# motor_driver.net
KiCad netlist of a schematic drawn in EAGLE
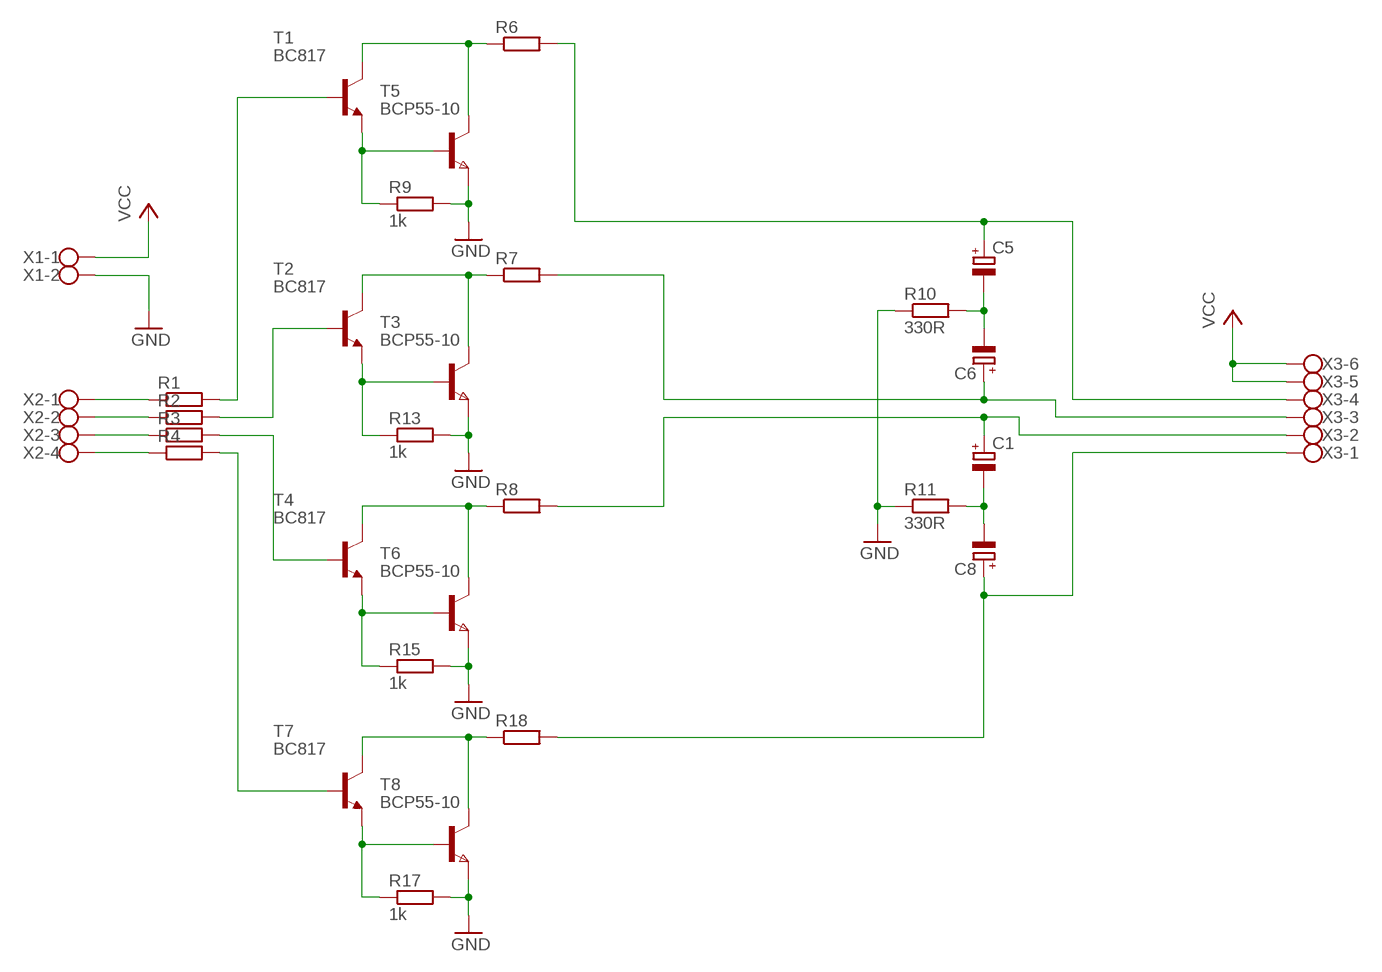
[diagram p0: schematic, sheet 1]

(export (version "E")
  (design (tool "Eeschema 10.0.6"))
  (components
    (comp (ref "C1")
      (value "CPOL-EU153CLV-0807")
      (footprint "eagle-import:153CLV-0807")
      (libsource (lib "eagle-import") (part "CPOL-EU153CLV-0807"))
    )
    (comp (ref "C5")
      (value "CPOL-EU153CLV-0807")
      (footprint "eagle-import:153CLV-0807")
      (libsource (lib "eagle-import") (part "CPOL-EU153CLV-0807"))
    )
    (comp (ref "C6")
      (value "CPOL-EU153CLV-0807")
      (footprint "eagle-import:153CLV-0807")
      (libsource (lib "eagle-import") (part "CPOL-EU153CLV-0807"))
    )
    (comp (ref "C8")
      (value "CPOL-EU153CLV-0807")
      (footprint "eagle-import:153CLV-0807")
      (libsource (lib "eagle-import") (part "CPOL-EU153CLV-0807"))
    )
    (comp (ref "R1")
      (value "R-EU_M1206")
      (footprint "eagle-import:M1206")
      (libsource (lib "eagle-import") (part "R-EU_M1206"))
    )
    (comp (ref "R2")
      (value "R-EU_M1206")
      (footprint "eagle-import:M1206")
      (libsource (lib "eagle-import") (part "R-EU_M1206"))
    )
    (comp (ref "R3")
      (value "R-EU_M1206")
      (footprint "eagle-import:M1206")
      (libsource (lib "eagle-import") (part "R-EU_M1206"))
    )
    (comp (ref "R4")
      (value "R-EU_M1206")
      (footprint "eagle-import:M1206")
      (libsource (lib "eagle-import") (part "R-EU_M1206"))
    )
    (comp (ref "R6")
      (value "R-EU_0922/22")
      (footprint "eagle-import:0922_22")
      (libsource (lib "eagle-import") (part "R-EU_0922/22"))
    )
    (comp (ref "R7")
      (value "R-EU_0922/22")
      (footprint "eagle-import:0922_22")
      (libsource (lib "eagle-import") (part "R-EU_0922/22"))
    )
    (comp (ref "R8")
      (value "R-EU_0922/22")
      (footprint "eagle-import:0922_22")
      (libsource (lib "eagle-import") (part "R-EU_0922/22"))
    )
    (comp (ref "R9")
      (value "1k")
      (footprint "eagle-import:M1206")
      (libsource (lib "eagle-import") (part "R-EU_M1206"))
    )
    (comp (ref "R10")
      (value "330R")
      (footprint "eagle-import:M1206")
      (libsource (lib "eagle-import") (part "R-EU_M1206"))
    )
    (comp (ref "R11")
      (value "330R")
      (footprint "eagle-import:M1206")
      (libsource (lib "eagle-import") (part "R-EU_M1206"))
    )
    (comp (ref "R13")
      (value "1k")
      (footprint "eagle-import:M1206")
      (libsource (lib "eagle-import") (part "R-EU_M1206"))
    )
    (comp (ref "R15")
      (value "1k")
      (footprint "eagle-import:M1206")
      (libsource (lib "eagle-import") (part "R-EU_M1206"))
    )
    (comp (ref "R17")
      (value "1k")
      (footprint "eagle-import:M1206")
      (libsource (lib "eagle-import") (part "R-EU_M1206"))
    )
    (comp (ref "R18")
      (value "R-EU_0922/22")
      (footprint "eagle-import:0922_22")
      (libsource (lib "eagle-import") (part "R-EU_0922/22"))
    )
    (comp (ref "T1")
      (value "BC817")
      (footprint "eagle-import:SOT23-BEC")
      (libsource (lib "eagle-import") (part "-NPN-SOT23-BECBC817-25"))
    )
    (comp (ref "T2")
      (value "BC817")
      (footprint "eagle-import:SOT23-BEC")
      (libsource (lib "eagle-import") (part "-NPN-SOT23-BECBC817-25"))
    )
    (comp (ref "T3")
      (value "BCP55-10")
      (footprint "eagle-import:SOT223")
      (fields (field (name "MPN") "DJT4031N-13"))
      (libsource (lib "eagle-import") (part "NPNSOT223"))
    )
    (comp (ref "T4")
      (value "BC817")
      (footprint "eagle-import:SOT23-BEC")
      (libsource (lib "eagle-import") (part "-NPN-SOT23-BECBC817-25"))
    )
    (comp (ref "T5")
      (value "BCP55-10")
      (footprint "eagle-import:SOT223")
      (fields (field (name "MPN") "DJT4031N-13"))
      (libsource (lib "eagle-import") (part "NPNSOT223"))
    )
    (comp (ref "T6")
      (value "BCP55-10")
      (footprint "eagle-import:SOT223")
      (fields (field (name "MPN") "DJT4031N-13"))
      (libsource (lib "eagle-import") (part "NPNSOT223"))
    )
    (comp (ref "T7")
      (value "BC817")
      (footprint "eagle-import:SOT23-BEC")
      (libsource (lib "eagle-import") (part "-NPN-SOT23-BECBC817-25"))
    )
    (comp (ref "T8")
      (value "BCP55-10")
      (footprint "eagle-import:SOT223")
      (fields (field (name "MPN") "DJT4031N-13"))
      (libsource (lib "eagle-import") (part "NPNSOT223"))
    )
    (comp (ref "X1")
      (value "W237-102")
      (footprint "eagle-import:W237-102")
      (fields (field (name "MPN") "237-102"))
      (libsource (lib "eagle-import") (part "W237-102"))
    )
    (comp (ref "X2")
      (value "W237-4")
      (footprint "eagle-import:W237-4")
      (libsource (lib "eagle-import") (part "W237-4"))
    )
    (comp (ref "X3")
      (value "W237-6")
      (footprint "eagle-import:W237-6")
      (libsource (lib "eagle-import") (part "W237-6"))
    )
  )
  (nets
    (net (code "1") (name "GND") (class "Default")
      (node (ref "R10") (pin "1") (pinfunction "1_1") (pintype "passive"))
      (node (ref "R11") (pin "1") (pinfunction "1_1") (pintype "passive"))
      (node (ref "R13") (pin "2") (pinfunction "2_2") (pintype "passive"))
      (node (ref "R15") (pin "2") (pinfunction "2_2") (pintype "passive"))
      (node (ref "R17") (pin "2") (pinfunction "2_2") (pintype "passive"))
      (node (ref "R9") (pin "2") (pinfunction "2_2") (pintype "passive"))
      (node (ref "T3") (pin "3") (pinfunction "E_3") (pintype "passive"))
      (node (ref "T5") (pin "3") (pinfunction "E_3") (pintype "passive"))
      (node (ref "T6") (pin "3") (pinfunction "E_3") (pintype "passive"))
      (node (ref "T8") (pin "3") (pinfunction "E_3") (pintype "passive"))
      (node (ref "X1") (pin "2") (pinfunction "KL_2") (pintype "passive"))
    )
    (net (code "2") (name "Net-(C1-Pad-)") (class "Default")
      (node (ref "C1") (pin "-") (pinfunction "-_-") (pintype "passive"))
      (node (ref "C8") (pin "-") (pinfunction "-_-") (pintype "passive"))
      (node (ref "R11") (pin "2") (pinfunction "2_2") (pintype "passive"))
    )
    (net (code "3") (name "Net-(C5-Pad-)") (class "Default")
      (node (ref "C5") (pin "-") (pinfunction "-_-") (pintype "passive"))
      (node (ref "C6") (pin "-") (pinfunction "-_-") (pintype "passive"))
      (node (ref "R10") (pin "2") (pinfunction "2_2") (pintype "passive"))
    )
    (net (code "4") (name "Net-(R1-Pad2)") (class "Default")
      (node (ref "R1") (pin "2") (pinfunction "2_2") (pintype "passive"))
      (node (ref "T1") (pin "B") (pinfunction "B_B") (pintype "passive"))
    )
    (net (code "5") (name "Net-(R2-Pad2)") (class "Default")
      (node (ref "R2") (pin "2") (pinfunction "2_2") (pintype "passive"))
      (node (ref "T2") (pin "B") (pinfunction "B_B") (pintype "passive"))
    )
    (net (code "6") (name "Net-(R3-Pad2)") (class "Default")
      (node (ref "R3") (pin "2") (pinfunction "2_2") (pintype "passive"))
      (node (ref "T4") (pin "B") (pinfunction "B_B") (pintype "passive"))
    )
    (net (code "7") (name "Net-(R4-Pad2)") (class "Default")
      (node (ref "R4") (pin "2") (pinfunction "2_2") (pintype "passive"))
      (node (ref "T7") (pin "B") (pinfunction "B_B") (pintype "passive"))
    )
    (net (code "8") (name "Net-(R6-Pad1)") (class "Default")
      (node (ref "R6") (pin "1") (pinfunction "1_1") (pintype "passive"))
      (node (ref "T1") (pin "C") (pinfunction "C_C") (pintype "passive"))
      (node (ref "T5") (pin "2") (pinfunction "C_2") (pintype "passive"))
      (node (ref "T5") (pin "4") (pinfunction "C_4") (pintype "passive"))
    )
    (net (code "9") (name "Net-(R7-Pad1)") (class "Default")
      (node (ref "R7") (pin "1") (pinfunction "1_1") (pintype "passive"))
      (node (ref "T2") (pin "C") (pinfunction "C_C") (pintype "passive"))
      (node (ref "T3") (pin "2") (pinfunction "C_2") (pintype "passive"))
      (node (ref "T3") (pin "4") (pinfunction "C_4") (pintype "passive"))
    )
    (net (code "10") (name "Net-(R8-Pad1)") (class "Default")
      (node (ref "R8") (pin "1") (pinfunction "1_1") (pintype "passive"))
      (node (ref "T4") (pin "C") (pinfunction "C_C") (pintype "passive"))
      (node (ref "T6") (pin "2") (pinfunction "C_2") (pintype "passive"))
      (node (ref "T6") (pin "4") (pinfunction "C_4") (pintype "passive"))
    )
    (net (code "11") (name "Net-(R18-Pad1)") (class "Default")
      (node (ref "R18") (pin "1") (pinfunction "1_1") (pintype "passive"))
      (node (ref "T7") (pin "C") (pinfunction "C_C") (pintype "passive"))
      (node (ref "T8") (pin "2") (pinfunction "C_2") (pintype "passive"))
      (node (ref "T8") (pin "4") (pinfunction "C_4") (pintype "passive"))
    )
    (net (code "12") (name "Net-(T3-B)") (class "Default")
      (node (ref "R13") (pin "1") (pinfunction "1_1") (pintype "passive"))
      (node (ref "T2") (pin "E") (pinfunction "E_E") (pintype "passive"))
      (node (ref "T3") (pin "1") (pinfunction "B_1") (pintype "passive"))
    )
    (net (code "13") (name "Net-(T5-B)") (class "Default")
      (node (ref "R9") (pin "1") (pinfunction "1_1") (pintype "passive"))
      (node (ref "T1") (pin "E") (pinfunction "E_E") (pintype "passive"))
      (node (ref "T5") (pin "1") (pinfunction "B_1") (pintype "passive"))
    )
    (net (code "14") (name "Net-(T6-B)") (class "Default")
      (node (ref "R15") (pin "1") (pinfunction "1_1") (pintype "passive"))
      (node (ref "T4") (pin "E") (pinfunction "E_E") (pintype "passive"))
      (node (ref "T6") (pin "1") (pinfunction "B_1") (pintype "passive"))
    )
    (net (code "15") (name "Net-(T8-B)") (class "Default")
      (node (ref "R17") (pin "1") (pinfunction "1_1") (pintype "passive"))
      (node (ref "T7") (pin "E") (pinfunction "E_E") (pintype "passive"))
      (node (ref "T8") (pin "1") (pinfunction "B_1") (pintype "passive"))
    )
    (net (code "16") (name "Net-(X2A-KL)") (class "Default")
      (node (ref "R1") (pin "1") (pinfunction "1_1") (pintype "passive"))
      (node (ref "X2") (pin "1") (pinfunction "KL_1") (pintype "passive"))
    )
    (net (code "17") (name "Net-(X2B-KL)") (class "Default")
      (node (ref "R2") (pin "1") (pinfunction "1_1") (pintype "passive"))
      (node (ref "X2") (pin "2") (pinfunction "KL_2") (pintype "passive"))
    )
    (net (code "18") (name "Net-(X2C-KL)") (class "Default")
      (node (ref "R3") (pin "1") (pinfunction "1_1") (pintype "passive"))
      (node (ref "X2") (pin "3") (pinfunction "KL_3") (pintype "passive"))
    )
    (net (code "19") (name "Net-(X2D-KL)") (class "Default")
      (node (ref "R4") (pin "1") (pinfunction "1_1") (pintype "passive"))
      (node (ref "X2") (pin "4") (pinfunction "KL_4") (pintype "passive"))
    )
    (net (code "20") (name "Net-(X3A-KL)") (class "Default")
      (node (ref "C8") (pin "+") (pinfunction "+_+") (pintype "passive"))
      (node (ref "R18") (pin "2") (pinfunction "2_2") (pintype "passive"))
      (node (ref "X3") (pin "1") (pinfunction "KL_1") (pintype "passive"))
    )
    (net (code "21") (name "Net-(X3B-KL)") (class "Default")
      (node (ref "C1") (pin "+") (pinfunction "+_+") (pintype "passive"))
      (node (ref "R8") (pin "2") (pinfunction "2_2") (pintype "passive"))
      (node (ref "X3") (pin "2") (pinfunction "KL_2") (pintype "passive"))
    )
    (net (code "22") (name "Net-(X3C-KL)") (class "Default")
      (node (ref "C6") (pin "+") (pinfunction "+_+") (pintype "passive"))
      (node (ref "R7") (pin "2") (pinfunction "2_2") (pintype "passive"))
      (node (ref "X3") (pin "3") (pinfunction "KL_3") (pintype "passive"))
    )
    (net (code "23") (name "Net-(X3D-KL)") (class "Default")
      (node (ref "C5") (pin "+") (pinfunction "+_+") (pintype "passive"))
      (node (ref "R6") (pin "2") (pinfunction "2_2") (pintype "passive"))
      (node (ref "X3") (pin "4") (pinfunction "KL_4") (pintype "passive"))
    )
    (net (code "24") (name "VCC") (class "Default")
      (node (ref "X1") (pin "1") (pinfunction "KL_1") (pintype "passive"))
      (node (ref "X3") (pin "5") (pinfunction "KL_5") (pintype "passive"))
      (node (ref "X3") (pin "6") (pinfunction "KL_6") (pintype "passive"))
    )
  )
)
